# 03_iMX_8X_PMIC.net
KiCad netlist of a schematic drawn in Altium Designer
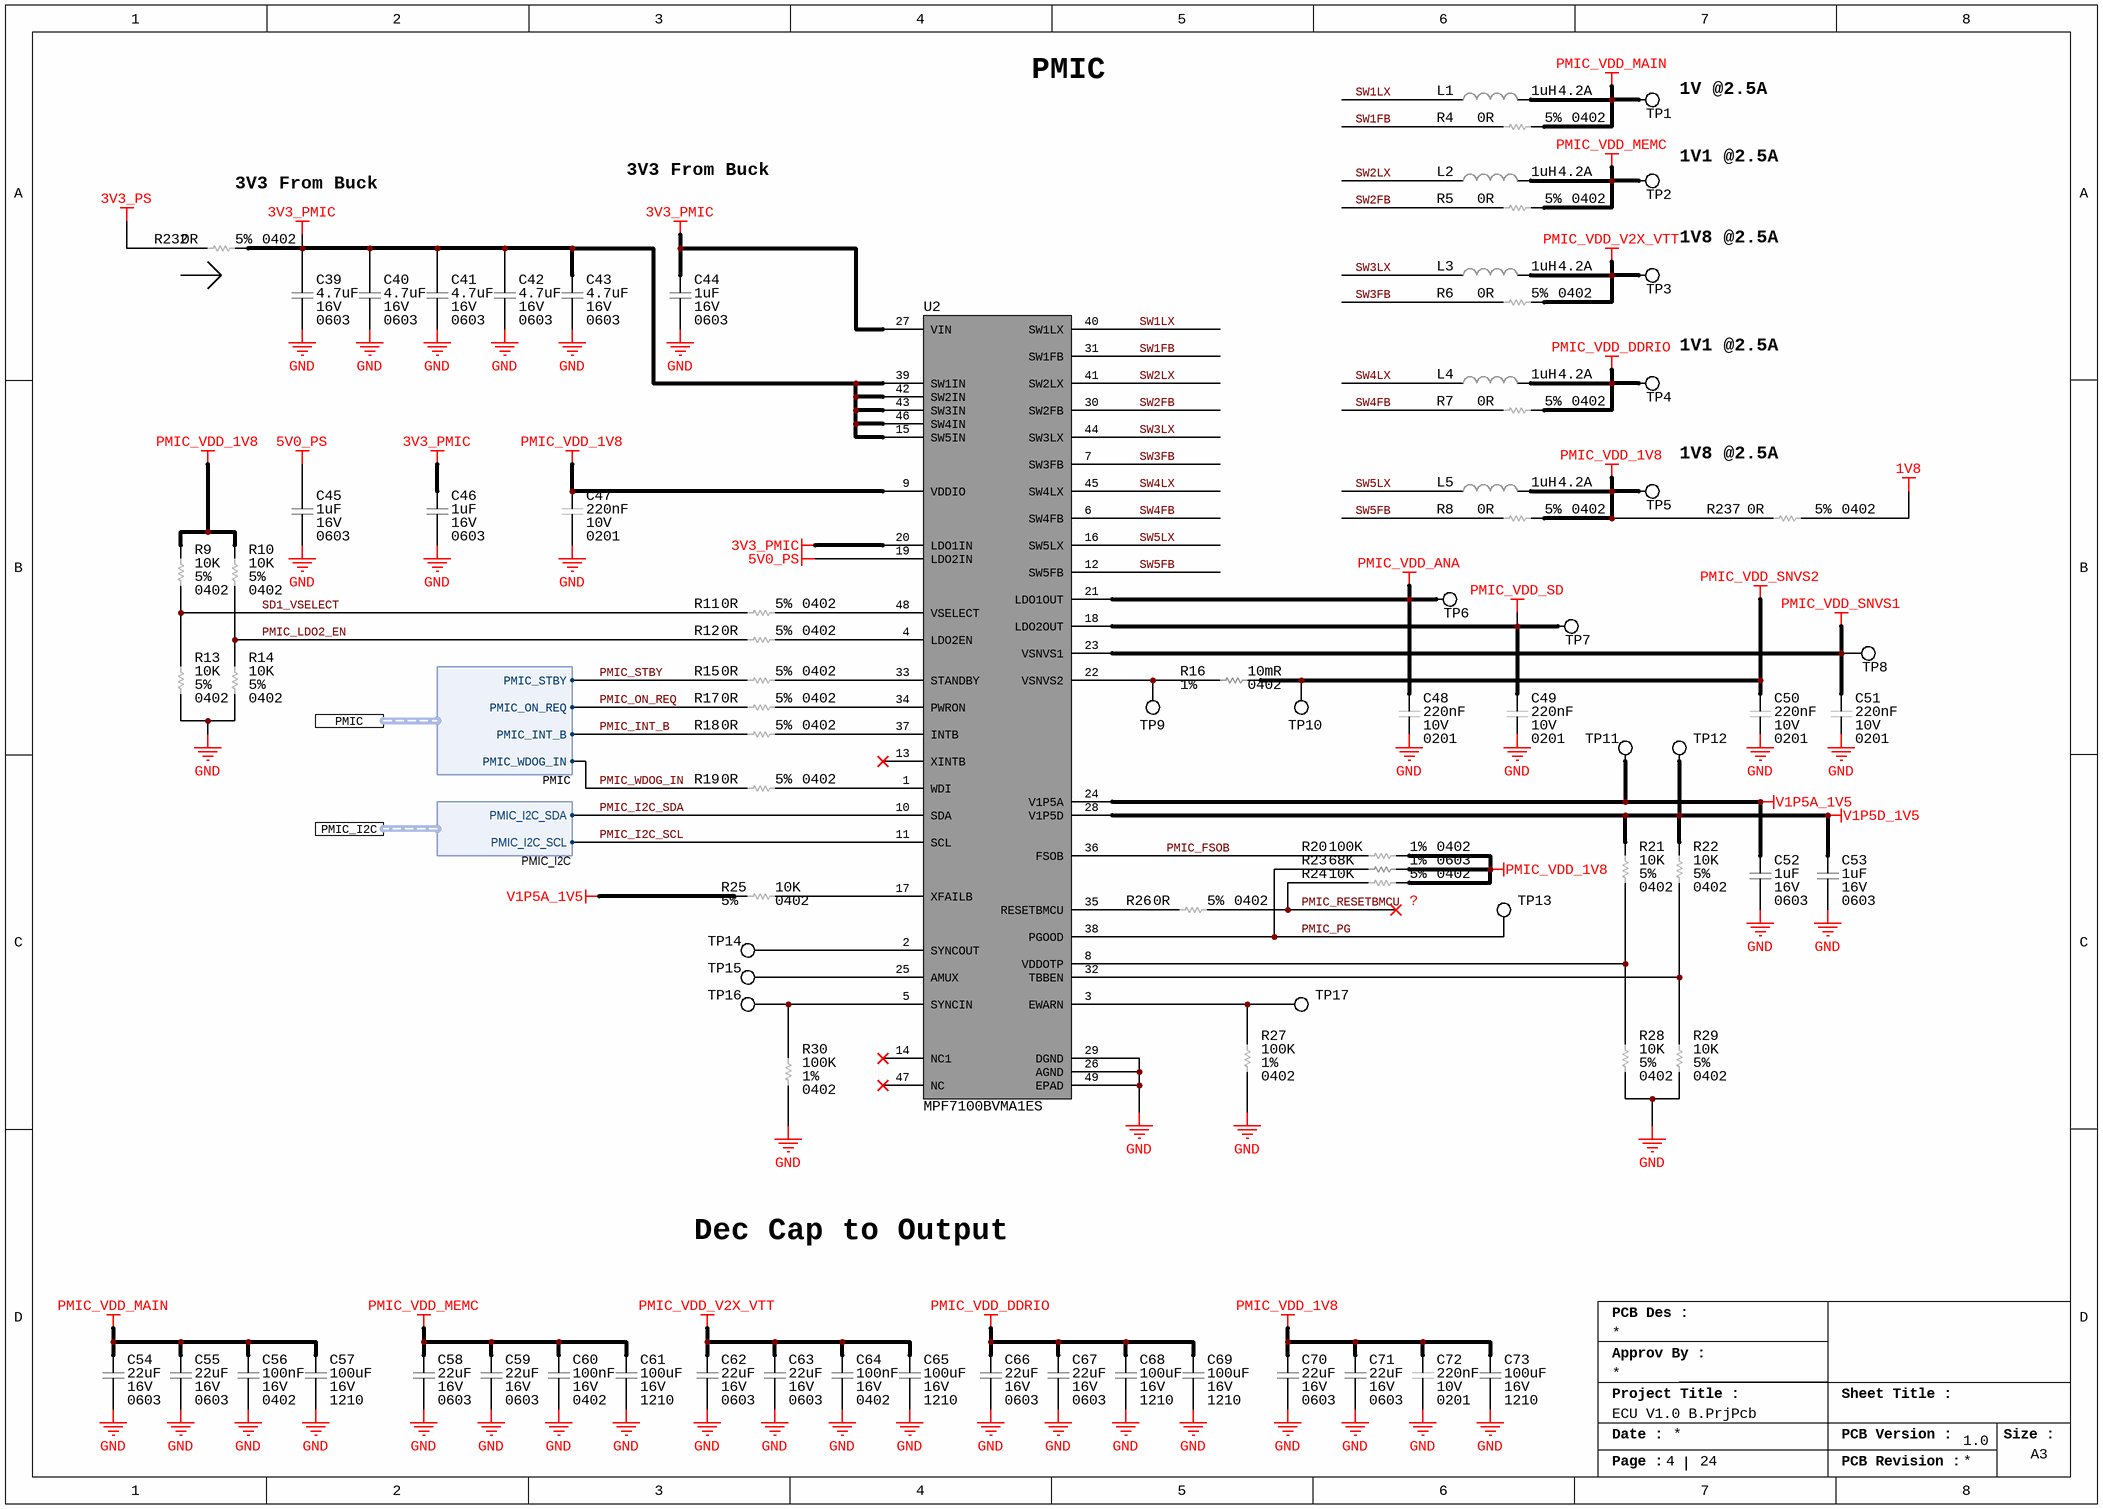
[diagram p0: 03_iMX 8X_PMIC.SchDoc]

(export (version "E")
  (design (tool "Eeschema 10.0.6"))
  (components
    (comp (ref "C39")
      (value "CL10A475KO8NNNC")
      (footprint "CAP_0603_CAPC1608X08N")
      (description "CAP CER 4.7UF 16V X5R 0603")
      (fields
        (field (name "MANUFACTURER") "Samsung")
        (field (name "TOLERANCE") "10%")
        (field (name "VOLTAGE") "16V")
        (field (name "CAPACITANCE") "4.7uF")
        (field (name "CASE/PACKAGE") "0603")
      )
      (libsource (lib "Electronic Devices_LIB") (part "CAP_4.7UF_16V_X5R_0603"))
    )
    (comp (ref "C40")
      (value "CL10A475KO8NNNC")
      (footprint "CAP_0603_CAPC1608X08N")
      (description "CAP CER 4.7UF 16V X5R 0603")
      (fields
        (field (name "MANUFACTURER") "Samsung")
        (field (name "TOLERANCE") "10%")
        (field (name "VOLTAGE") "16V")
        (field (name "CAPACITANCE") "4.7uF")
        (field (name "CASE/PACKAGE") "0603")
      )
      (libsource (lib "Electronic Devices_LIB") (part "CAP_4.7UF_16V_X5R_0603"))
    )
    (comp (ref "C41")
      (value "CL10A475KO8NNNC")
      (footprint "CAP_0603_CAPC1608X08N")
      (description "CAP CER 4.7UF 16V X5R 0603")
      (fields
        (field (name "MANUFACTURER") "Samsung")
        (field (name "TOLERANCE") "10%")
        (field (name "VOLTAGE") "16V")
        (field (name "CAPACITANCE") "4.7uF")
        (field (name "CASE/PACKAGE") "0603")
      )
      (libsource (lib "Electronic Devices_LIB") (part "CAP_4.7UF_16V_X5R_0603"))
    )
    (comp (ref "C42")
      (value "CL10A475KO8NNNC")
      (footprint "CAP_0603_CAPC1608X08N")
      (description "CAP CER 4.7UF 16V X5R 0603")
      (fields
        (field (name "MANUFACTURER") "Samsung")
        (field (name "TOLERANCE") "10%")
        (field (name "VOLTAGE") "16V")
        (field (name "CAPACITANCE") "4.7uF")
        (field (name "CASE/PACKAGE") "0603")
      )
      (libsource (lib "Electronic Devices_LIB") (part "CAP_4.7UF_16V_X5R_0603"))
    )
    (comp (ref "C43")
      (value "CL10A475KO8NNNC")
      (footprint "CAP_0603_CAPC1608X08N")
      (description "CAP CER 4.7UF 16V X5R 0603")
      (fields
        (field (name "MANUFACTURER") "Samsung")
        (field (name "TOLERANCE") "10%")
        (field (name "VOLTAGE") "16V")
        (field (name "CAPACITANCE") "4.7uF")
        (field (name "CASE/PACKAGE") "0603")
      )
      (libsource (lib "Electronic Devices_LIB") (part "CAP_4.7UF_16V_X5R_0603"))
    )
    (comp (ref "C44")
      (value "CL10A105KO8NNNC")
      (footprint "CAP_0603_CAPC1608X08N")
      (description "CAP CER 1UF 16V X5R 0603")
      (fields
        (field (name "MANUFACTURER") "Samsung")
        (field (name "TOLERANCE") "10%")
        (field (name "VOLTAGE RATING") "16V")
        (field (name "CAPACITANCE") "1uF")
        (field (name "CASE/PACKAGE") "0603")
      )
      (libsource (lib "Electronic Devices_LIB") (part "CAP_1UF_16V_X5R_0603"))
    )
    (comp (ref "C45")
      (value "CL10A105KO8NNNC")
      (footprint "CAP_0603_CAPC1608X08N")
      (description "CAP CER 1UF 16V X5R 0603")
      (fields
        (field (name "MANUFACTURER") "Samsung")
        (field (name "TOLERANCE") "10%")
        (field (name "VOLTAGE RATING") "16V")
        (field (name "CAPACITANCE") "1uF")
        (field (name "CASE/PACKAGE") "0603")
      )
      (libsource (lib "Electronic Devices_LIB") (part "CAP_1UF_16V_X5R_0603"))
    )
    (comp (ref "C46")
      (value "CL10A105KO8NNNC")
      (footprint "CAP_0603_CAPC1608X08N")
      (description "CAP CER 1UF 16V X5R 0603")
      (fields
        (field (name "MANUFACTURER") "Samsung")
        (field (name "TOLERANCE") "10%")
        (field (name "VOLTAGE RATING") "16V")
        (field (name "CAPACITANCE") "1uF")
        (field (name "CASE/PACKAGE") "0603")
      )
      (libsource (lib "Electronic Devices_LIB") (part "CAP_1UF_16V_X5R_0603"))
    )
    (comp (ref "C47")
      (value "LMK063BJ224MP-F")
      (footprint "CAP_0201_CAPC0603X03N")
      (description "Multilayer Ceramic Capacitors (High dielectric type), 10V, 0.22 uF, ± 20 %, 0201, X5R, RoHS")
      (fields
        (field (name "MANUFACTURER") "Taiyo Yuden")
        (field (name "TOLERANCE") "20%")
        (field (name "VOLTAGE RATING (DC)") "10V")
        (field (name "CAPACITANCE") "220nF")
        (field (name "CASE/PACKAGE") "0201")
      )
      (libsource (lib "Electronic Devices_LIB") (part "CAP_0.22UF_10V_X5R_0201"))
    )
    (comp (ref "C48")
      (value "LMK063BJ224MP-F")
      (footprint "CAP_0201_CAPC0603X03N")
      (description "Multilayer Ceramic Capacitors (High dielectric type), 10V, 0.22 uF, ± 20 %, 0201, X5R, RoHS")
      (fields
        (field (name "MANUFACTURER") "Taiyo Yuden")
        (field (name "TOLERANCE") "20%")
        (field (name "VOLTAGE RATING (DC)") "10V")
        (field (name "CAPACITANCE") "220nF")
        (field (name "CASE/PACKAGE") "0201")
      )
      (libsource (lib "Electronic Devices_LIB") (part "CAP_0.22UF_10V_X5R_0201"))
    )
    (comp (ref "C49")
      (value "LMK063BJ224MP-F")
      (footprint "CAP_0201_CAPC0603X03N")
      (description "Multilayer Ceramic Capacitors (High dielectric type), 10V, 0.22 uF, ± 20 %, 0201, X5R, RoHS")
      (fields
        (field (name "MANUFACTURER") "Taiyo Yuden")
        (field (name "TOLERANCE") "20%")
        (field (name "VOLTAGE RATING (DC)") "10V")
        (field (name "CAPACITANCE") "220nF")
        (field (name "CASE/PACKAGE") "0201")
      )
      (libsource (lib "Electronic Devices_LIB") (part "CAP_0.22UF_10V_X5R_0201"))
    )
    (comp (ref "C50")
      (value "LMK063BJ224MP-F")
      (footprint "CAP_0201_CAPC0603X03N")
      (description "Multilayer Ceramic Capacitors (High dielectric type), 10V, 0.22 uF, ± 20 %, 0201, X5R, RoHS")
      (fields
        (field (name "MANUFACTURER") "Taiyo Yuden")
        (field (name "TOLERANCE") "20%")
        (field (name "VOLTAGE RATING (DC)") "10V")
        (field (name "CAPACITANCE") "220nF")
        (field (name "CASE/PACKAGE") "0201")
      )
      (libsource (lib "Electronic Devices_LIB") (part "CAP_0.22UF_10V_X5R_0201"))
    )
    (comp (ref "C51")
      (value "LMK063BJ224MP-F")
      (footprint "CAP_0201_CAPC0603X03N")
      (description "Multilayer Ceramic Capacitors (High dielectric type), 10V, 0.22 uF, ± 20 %, 0201, X5R, RoHS")
      (fields
        (field (name "MANUFACTURER") "Taiyo Yuden")
        (field (name "TOLERANCE") "20%")
        (field (name "VOLTAGE RATING (DC)") "10V")
        (field (name "CAPACITANCE") "220nF")
        (field (name "CASE/PACKAGE") "0201")
      )
      (libsource (lib "Electronic Devices_LIB") (part "CAP_0.22UF_10V_X5R_0201"))
    )
    (comp (ref "C52")
      (value "CL10A105KO8NNNC")
      (footprint "CAP_0603_CAPC1608X08N")
      (description "CAP CER 1UF 16V X5R 0603")
      (fields
        (field (name "MANUFACTURER") "Samsung")
        (field (name "TOLERANCE") "10%")
        (field (name "VOLTAGE RATING") "16V")
        (field (name "CAPACITANCE") "1uF")
        (field (name "CASE/PACKAGE") "0603")
      )
      (libsource (lib "Electronic Devices_LIB") (part "CAP_1UF_16V_X5R_0603"))
    )
    (comp (ref "C53")
      (value "CL10A105KO8NNNC")
      (footprint "CAP_0603_CAPC1608X08N")
      (description "CAP CER 1UF 16V X5R 0603")
      (fields
        (field (name "MANUFACTURER") "Samsung")
        (field (name "TOLERANCE") "10%")
        (field (name "VOLTAGE RATING") "16V")
        (field (name "CAPACITANCE") "1uF")
        (field (name "CASE/PACKAGE") "0603")
      )
      (libsource (lib "Electronic Devices_LIB") (part "CAP_1UF_16V_X5R_0603"))
    )
    (comp (ref "C54")
      (value "CL10A226MO7JZNC")
      (footprint "CAP_0603_CAPC1608X08N")
      (description "Cap Ceramic 22uF 16V X5R 20% Pad SMD 0603 85C T/R")
      (fields
        (field (name "MANUFACTURER") "Samsung")
        (field (name "TOLERANCE") "20%")
        (field (name "CAPACITANCE") "22uF")
        (field (name "VOLTAGE RATING") "16V")
        (field (name "CASE/PACKAGE") "0603")
      )
      (libsource (lib "Electronic Devices_LIB") (part "CAP_22UF_16V_X5R_0603"))
    )
    (comp (ref "C55")
      (value "CL10A226MO7JZNC")
      (footprint "CAP_0603_CAPC1608X08N")
      (description "Cap Ceramic 22uF 16V X5R 20% Pad SMD 0603 85C T/R")
      (fields
        (field (name "MANUFACTURER") "Samsung")
        (field (name "TOLERANCE") "20%")
        (field (name "CAPACITANCE") "22uF")
        (field (name "VOLTAGE RATING") "16V")
        (field (name "CASE/PACKAGE") "0603")
      )
      (libsource (lib "Electronic Devices_LIB") (part "CAP_22UF_16V_X5R_0603"))
    )
    (comp (ref "C56")
      (value "CL05B104KO5NNNC")
      (footprint "CAP_0402_CAPC1005X05N")
      (description "Multilayer Ceramic Capacitor, 0.1 uF, 16 V, ± 10%, X7R, 0402 [1005 Metric]")
      (fields
        (field (name "MANUFACTURER") "Samsung")
        (field (name "TOLERANCE") "10%")
        (field (name "VOLTAGE RATING") "16V")
        (field (name "CAPACITANCE") "100nF")
        (field (name "CASE/PACKAGE") "0402")
      )
      (libsource (lib "Electronic Devices_LIB") (part "CAP_100NF_16V_X7R_0402"))
    )
    (comp (ref "C57")
      (value "EMK325ABJ107MM-T")
      (footprint "CAP_1210_CAPC3225X270N")
      (description "Multilayer Ceramic Capacitor, 100 uF, 16 V, ± 20%, X5R, 1210 [3225 Metric]")
      (fields
        (field (name "MANUFACTURER") "Taiyo Yuden")
        (field (name "TOLERANCE") "20%")
        (field (name "VOLTAGE RATING") "16V")
        (field (name "CAPACITANCE") "100uF")
        (field (name "CASE/PACKAGE") "1210")
      )
      (libsource (lib "Electronic Devices_LIB") (part "CAP_100UF_16V_X5R_1210"))
    )
    (comp (ref "C58")
      (value "CL10A226MO7JZNC")
      (footprint "CAP_0603_CAPC1608X08N")
      (description "Cap Ceramic 22uF 16V X5R 20% Pad SMD 0603 85C T/R")
      (fields
        (field (name "MANUFACTURER") "Samsung")
        (field (name "TOLERANCE") "20%")
        (field (name "CAPACITANCE") "22uF")
        (field (name "VOLTAGE RATING") "16V")
        (field (name "CASE/PACKAGE") "0603")
      )
      (libsource (lib "Electronic Devices_LIB") (part "CAP_22UF_16V_X5R_0603"))
    )
    (comp (ref "C59")
      (value "CL10A226MO7JZNC")
      (footprint "CAP_0603_CAPC1608X08N")
      (description "Cap Ceramic 22uF 16V X5R 20% Pad SMD 0603 85C T/R")
      (fields
        (field (name "MANUFACTURER") "Samsung")
        (field (name "TOLERANCE") "20%")
        (field (name "CAPACITANCE") "22uF")
        (field (name "VOLTAGE RATING") "16V")
        (field (name "CASE/PACKAGE") "0603")
      )
      (libsource (lib "Electronic Devices_LIB") (part "CAP_22UF_16V_X5R_0603"))
    )
    (comp (ref "C60")
      (value "CL05B104KO5NNNC")
      (footprint "CAP_0402_CAPC1005X05N")
      (description "Multilayer Ceramic Capacitor, 0.1 uF, 16 V, ± 10%, X7R, 0402 [1005 Metric]")
      (fields
        (field (name "MANUFACTURER") "Samsung")
        (field (name "TOLERANCE") "10%")
        (field (name "VOLTAGE RATING") "16V")
        (field (name "CAPACITANCE") "100nF")
        (field (name "CASE/PACKAGE") "0402")
      )
      (libsource (lib "Electronic Devices_LIB") (part "CAP_100NF_16V_X7R_0402"))
    )
    (comp (ref "C61")
      (value "EMK325ABJ107MM-T")
      (footprint "CAP_1210_CAPC3225X270N")
      (description "Multilayer Ceramic Capacitor, 100 uF, 16 V, ± 20%, X5R, 1210 [3225 Metric]")
      (fields
        (field (name "MANUFACTURER") "Taiyo Yuden")
        (field (name "TOLERANCE") "20%")
        (field (name "VOLTAGE RATING") "16V")
        (field (name "CAPACITANCE") "100uF")
        (field (name "CASE/PACKAGE") "1210")
      )
      (libsource (lib "Electronic Devices_LIB") (part "CAP_100UF_16V_X5R_1210"))
    )
    (comp (ref "C62")
      (value "CL10A226MO7JZNC")
      (footprint "CAP_0603_CAPC1608X08N")
      (description "Cap Ceramic 22uF 16V X5R 20% Pad SMD 0603 85C T/R")
      (fields
        (field (name "MANUFACTURER") "Samsung")
        (field (name "TOLERANCE") "20%")
        (field (name "CAPACITANCE") "22uF")
        (field (name "VOLTAGE RATING") "16V")
        (field (name "CASE/PACKAGE") "0603")
      )
      (libsource (lib "Electronic Devices_LIB") (part "CAP_22UF_16V_X5R_0603"))
    )
    (comp (ref "C63")
      (value "CL10A226MO7JZNC")
      (footprint "CAP_0603_CAPC1608X08N")
      (description "Cap Ceramic 22uF 16V X5R 20% Pad SMD 0603 85C T/R")
      (fields
        (field (name "MANUFACTURER") "Samsung")
        (field (name "TOLERANCE") "20%")
        (field (name "CAPACITANCE") "22uF")
        (field (name "VOLTAGE RATING") "16V")
        (field (name "CASE/PACKAGE") "0603")
      )
      (libsource (lib "Electronic Devices_LIB") (part "CAP_22UF_16V_X5R_0603"))
    )
    (comp (ref "C64")
      (value "CL05B104KO5NNNC")
      (footprint "CAP_0402_CAPC1005X05N")
      (description "Multilayer Ceramic Capacitor, 0.1 uF, 16 V, ± 10%, X7R, 0402 [1005 Metric]")
      (fields
        (field (name "MANUFACTURER") "Samsung")
        (field (name "TOLERANCE") "10%")
        (field (name "VOLTAGE RATING") "16V")
        (field (name "CAPACITANCE") "100nF")
        (field (name "CASE/PACKAGE") "0402")
      )
      (libsource (lib "Electronic Devices_LIB") (part "CAP_100NF_16V_X7R_0402"))
    )
    (comp (ref "C65")
      (value "EMK325ABJ107MM-T")
      (footprint "CAP_1210_CAPC3225X270N")
      (description "Multilayer Ceramic Capacitor, 100 uF, 16 V, ± 20%, X5R, 1210 [3225 Metric]")
      (fields
        (field (name "MANUFACTURER") "Taiyo Yuden")
        (field (name "TOLERANCE") "20%")
        (field (name "VOLTAGE RATING") "16V")
        (field (name "CAPACITANCE") "100uF")
        (field (name "CASE/PACKAGE") "1210")
      )
      (libsource (lib "Electronic Devices_LIB") (part "CAP_100UF_16V_X5R_1210"))
    )
    (comp (ref "C66")
      (value "CL10A226MO7JZNC")
      (footprint "CAP_0603_CAPC1608X08N")
      (description "Cap Ceramic 22uF 16V X5R 20% Pad SMD 0603 85C T/R")
      (fields
        (field (name "MANUFACTURER") "Samsung")
        (field (name "TOLERANCE") "20%")
        (field (name "CAPACITANCE") "22uF")
        (field (name "VOLTAGE RATING") "16V")
        (field (name "CASE/PACKAGE") "0603")
      )
      (libsource (lib "Electronic Devices_LIB") (part "CAP_22UF_16V_X5R_0603"))
    )
    (comp (ref "C67")
      (value "CL10A226MO7JZNC")
      (footprint "CAP_0603_CAPC1608X08N")
      (description "Cap Ceramic 22uF 16V X5R 20% Pad SMD 0603 85C T/R")
      (fields
        (field (name "MANUFACTURER") "Samsung")
        (field (name "TOLERANCE") "20%")
        (field (name "CAPACITANCE") "22uF")
        (field (name "VOLTAGE RATING") "16V")
        (field (name "CASE/PACKAGE") "0603")
      )
      (libsource (lib "Electronic Devices_LIB") (part "CAP_22UF_16V_X5R_0603"))
    )
    (comp (ref "C68")
      (value "EMK325ABJ107MM-T")
      (footprint "CAP_1210_CAPC3225X270N")
      (description "Multilayer Ceramic Capacitor, 100 uF, 16 V, ± 20%, X5R, 1210 [3225 Metric]")
      (fields
        (field (name "MANUFACTURER") "Taiyo Yuden")
        (field (name "TOLERANCE") "20%")
        (field (name "VOLTAGE RATING") "16V")
        (field (name "CAPACITANCE") "100uF")
        (field (name "CASE/PACKAGE") "1210")
      )
      (libsource (lib "Electronic Devices_LIB") (part "CAP_100UF_16V_X5R_1210"))
    )
    (comp (ref "C69")
      (value "EMK325ABJ107MM-T")
      (footprint "CAP_1210_CAPC3225X270N")
      (description "Multilayer Ceramic Capacitor, 100 uF, 16 V, ± 20%, X5R, 1210 [3225 Metric]")
      (fields
        (field (name "MANUFACTURER") "Taiyo Yuden")
        (field (name "TOLERANCE") "20%")
        (field (name "VOLTAGE RATING") "16V")
        (field (name "CAPACITANCE") "100uF")
        (field (name "CASE/PACKAGE") "1210")
      )
      (libsource (lib "Electronic Devices_LIB") (part "CAP_100UF_16V_X5R_1210"))
    )
    (comp (ref "C70")
      (value "CL10A226MO7JZNC")
      (footprint "CAP_0603_CAPC1608X08N")
      (description "Cap Ceramic 22uF 16V X5R 20% Pad SMD 0603 85C T/R")
      (fields
        (field (name "MANUFACTURER") "Samsung")
        (field (name "TOLERANCE") "20%")
        (field (name "CAPACITANCE") "22uF")
        (field (name "VOLTAGE RATING") "16V")
        (field (name "CASE/PACKAGE") "0603")
      )
      (libsource (lib "Electronic Devices_LIB") (part "CAP_22UF_16V_X5R_0603"))
    )
    (comp (ref "C71")
      (value "CL10A226MO7JZNC")
      (footprint "CAP_0603_CAPC1608X08N")
      (description "Cap Ceramic 22uF 16V X5R 20% Pad SMD 0603 85C T/R")
      (fields
        (field (name "MANUFACTURER") "Samsung")
        (field (name "TOLERANCE") "20%")
        (field (name "CAPACITANCE") "22uF")
        (field (name "VOLTAGE RATING") "16V")
        (field (name "CASE/PACKAGE") "0603")
      )
      (libsource (lib "Electronic Devices_LIB") (part "CAP_22UF_16V_X5R_0603"))
    )
    (comp (ref "C72")
      (value "LMK063BJ224MP-F")
      (footprint "CAP_0201_CAPC0603X03N")
      (description "Multilayer Ceramic Capacitors (High dielectric type), 10V, 0.22 uF, ± 20 %, 0201, X5R, RoHS")
      (fields
        (field (name "MANUFACTURER") "Taiyo Yuden")
        (field (name "TOLERANCE") "20%")
        (field (name "VOLTAGE RATING (DC)") "10V")
        (field (name "CAPACITANCE") "220nF")
        (field (name "CASE/PACKAGE") "0201")
      )
      (libsource (lib "Electronic Devices_LIB") (part "CAP_0.22UF_10V_X5R_0201"))
    )
    (comp (ref "C73")
      (value "EMK325ABJ107MM-T")
      (footprint "CAP_1210_CAPC3225X270N")
      (description "Multilayer Ceramic Capacitor, 100 uF, 16 V, ± 20%, X5R, 1210 [3225 Metric]")
      (fields
        (field (name "MANUFACTURER") "Taiyo Yuden")
        (field (name "TOLERANCE") "20%")
        (field (name "VOLTAGE RATING") "16V")
        (field (name "CAPACITANCE") "100uF")
        (field (name "CASE/PACKAGE") "1210")
      )
      (libsource (lib "Electronic Devices_LIB") (part "CAP_100UF_16V_X5R_1210"))
    )
    (comp (ref "L1")
      (value "TFM252012ALMA1R0MTAA")
      (footprint "INDC2520X120N")
      (description "Inductor Power Shielded Thin Film 1uH 20% 1MHz Metal 3.7A 0.042Ohm DCR 1008 Automotive T/R")
      (fields
        (field (name "MANUFACTURER") "TDK")
        (field (name "TOLERANCE") "20%")
        (field (name "SATURATION CURRENT") "4.2A")
        (field (name "INDUCTANCE") "1uH")
      )
      (libsource (lib "Electronic Devices_LIB") (part "IND_1uH_3.7A_TFM252012ALMA1R0MTAA"))
    )
    (comp (ref "L2")
      (value "TFM252012ALMA1R0MTAA")
      (footprint "INDC2520X120N")
      (description "Inductor Power Shielded Thin Film 1uH 20% 1MHz Metal 3.7A 0.042Ohm DCR 1008 Automotive T/R")
      (fields
        (field (name "MANUFACTURER") "TDK")
        (field (name "TOLERANCE") "20%")
        (field (name "SATURATION CURRENT") "4.2A")
        (field (name "INDUCTANCE") "1uH")
      )
      (libsource (lib "Electronic Devices_LIB") (part "IND_1uH_3.7A_TFM252012ALMA1R0MTAA"))
    )
    (comp (ref "L3")
      (value "TFM252012ALMA1R0MTAA")
      (footprint "INDC2520X120N")
      (description "Inductor Power Shielded Thin Film 1uH 20% 1MHz Metal 3.7A 0.042Ohm DCR 1008 Automotive T/R")
      (fields
        (field (name "MANUFACTURER") "TDK")
        (field (name "TOLERANCE") "20%")
        (field (name "SATURATION CURRENT") "4.2A")
        (field (name "INDUCTANCE") "1uH")
      )
      (libsource (lib "Electronic Devices_LIB") (part "IND_1uH_3.7A_TFM252012ALMA1R0MTAA"))
    )
    (comp (ref "L4")
      (value "TFM252012ALMA1R0MTAA")
      (footprint "INDC2520X120N")
      (description "Inductor Power Shielded Thin Film 1uH 20% 1MHz Metal 3.7A 0.042Ohm DCR 1008 Automotive T/R")
      (fields
        (field (name "MANUFACTURER") "TDK")
        (field (name "TOLERANCE") "20%")
        (field (name "SATURATION CURRENT") "4.2A")
        (field (name "INDUCTANCE") "1uH")
      )
      (libsource (lib "Electronic Devices_LIB") (part "IND_1uH_3.7A_TFM252012ALMA1R0MTAA"))
    )
    (comp (ref "L5")
      (value "TFM252012ALMA1R0MTAA")
      (footprint "INDC2520X120N")
      (description "Inductor Power Shielded Thin Film 1uH 20% 1MHz Metal 3.7A 0.042Ohm DCR 1008 Automotive T/R")
      (fields
        (field (name "MANUFACTURER") "TDK")
        (field (name "TOLERANCE") "20%")
        (field (name "SATURATION CURRENT") "4.2A")
        (field (name "INDUCTANCE") "1uH")
      )
      (libsource (lib "Electronic Devices_LIB") (part "IND_1uH_3.7A_TFM252012ALMA1R0MTAA"))
    )
    (comp (ref "R4")
      (value "ERJ-2GE0R00X")
      (footprint "RES_0402_RESC1005X04N")
      (description "SMD Chip Resistor, Jumper, 0 ohm, 100 mW, 0402 [1005 Metric], Thick Film, General Purpose")
      (fields
        (field (name "MANUFACTURER") "Panasonic")
        (field (name "CASE CODE (IMPERIAL)") "0402")
        (field (name "TOLERANCE") "5%")
        (field (name "RESISTANCE") "0R")
      )
      (libsource (lib "Electronic Devices_LIB") (part "RES_0R_5%_100mW_0402"))
    )
    (comp (ref "R5")
      (value "ERJ-2GE0R00X")
      (footprint "RES_0402_RESC1005X04N")
      (description "SMD Chip Resistor, Jumper, 0 ohm, 100 mW, 0402 [1005 Metric], Thick Film, General Purpose")
      (fields
        (field (name "MANUFACTURER") "Panasonic")
        (field (name "CASE CODE (IMPERIAL)") "0402")
        (field (name "TOLERANCE") "5%")
        (field (name "RESISTANCE") "0R")
      )
      (libsource (lib "Electronic Devices_LIB") (part "RES_0R_5%_100mW_0402"))
    )
    (comp (ref "R6")
      (value "ERJ-2GE0R00X")
      (footprint "RES_0402_RESC1005X04N")
      (description "SMD Chip Resistor, Jumper, 0 ohm, 100 mW, 0402 [1005 Metric], Thick Film, General Purpose")
      (fields
        (field (name "MANUFACTURER") "Panasonic")
        (field (name "CASE CODE (IMPERIAL)") "0402")
        (field (name "TOLERANCE") "5%")
        (field (name "RESISTANCE") "0R")
      )
      (libsource (lib "Electronic Devices_LIB") (part "RES_0R_5%_100mW_0402"))
    )
    (comp (ref "R7")
      (value "ERJ-2GE0R00X")
      (footprint "RES_0402_RESC1005X04N")
      (description "SMD Chip Resistor, Jumper, 0 ohm, 100 mW, 0402 [1005 Metric], Thick Film, General Purpose")
      (fields
        (field (name "MANUFACTURER") "Panasonic")
        (field (name "CASE CODE (IMPERIAL)") "0402")
        (field (name "TOLERANCE") "5%")
        (field (name "RESISTANCE") "0R")
      )
      (libsource (lib "Electronic Devices_LIB") (part "RES_0R_5%_100mW_0402"))
    )
    (comp (ref "R8")
      (value "ERJ-2GE0R00X")
      (footprint "RES_0402_RESC1005X04N")
      (description "SMD Chip Resistor, Jumper, 0 ohm, 100 mW, 0402 [1005 Metric], Thick Film, General Purpose")
      (fields
        (field (name "MANUFACTURER") "Panasonic")
        (field (name "CASE CODE (IMPERIAL)") "0402")
        (field (name "TOLERANCE") "5%")
        (field (name "RESISTANCE") "0R")
      )
      (libsource (lib "Electronic Devices_LIB") (part "RES_0R_5%_100mW_0402"))
    )
    (comp (ref "R9")
      (value "ERJ-2GEJ103X")
      (footprint "RES_0402_RESC1005X04N")
      (description "Res Thick Film 0402 10K Ohm 5% 1/10W ±200ppm/°C Molded SMD Punched Carrier T/R")
      (fields
        (field (name "MANUFACTURER") "Panasonic")
        (field (name "TOLERANCE") "5%")
        (field (name "RESISTANCE") "10K")
        (field (name "CASE/PACKAGE") "0402")
      )
      (libsource (lib "Electronic Devices_LIB") (part "RES_10K_5%_100mW_0402"))
    )
    (comp (ref "R10")
      (value "ERJ-2GEJ103X")
      (footprint "RES_0402_RESC1005X04N")
      (description "Res Thick Film 0402 10K Ohm 5% 1/10W ±200ppm/°C Molded SMD Punched Carrier T/R")
      (fields
        (field (name "MANUFACTURER") "Panasonic")
        (field (name "TOLERANCE") "5%")
        (field (name "RESISTANCE") "10K")
        (field (name "CASE/PACKAGE") "0402")
      )
      (libsource (lib "Electronic Devices_LIB") (part "RES_10K_5%_100mW_0402"))
    )
    (comp (ref "R11")
      (value "ERJ-2GE0R00X")
      (footprint "RES_0402_RESC1005X04N")
      (description "SMD Chip Resistor, Jumper, 0 ohm, 100 mW, 0402 [1005 Metric], Thick Film, General Purpose")
      (fields
        (field (name "MANUFACTURER") "Panasonic")
        (field (name "CASE CODE (IMPERIAL)") "0402")
        (field (name "TOLERANCE") "5%")
        (field (name "RESISTANCE") "0R")
      )
      (libsource (lib "Electronic Devices_LIB") (part "RES_0R_5%_100mW_0402"))
    )
    (comp (ref "R12")
      (value "ERJ-2GE0R00X")
      (footprint "RES_0402_RESC1005X04N")
      (description "SMD Chip Resistor, Jumper, 0 ohm, 100 mW, 0402 [1005 Metric], Thick Film, General Purpose")
      (fields
        (field (name "MANUFACTURER") "Panasonic")
        (field (name "CASE CODE (IMPERIAL)") "0402")
        (field (name "TOLERANCE") "5%")
        (field (name "RESISTANCE") "0R")
      )
      (libsource (lib "Electronic Devices_LIB") (part "RES_0R_5%_100mW_0402"))
    )
    (comp (ref "R13")
      (value "ERJ-2GEJ103X")
      (footprint "RES_0402_RESC1005X04N")
      (description "Res Thick Film 0402 10K Ohm 5% 1/10W ±200ppm/°C Molded SMD Punched Carrier T/R")
      (fields
        (field (name "MANUFACTURER") "Panasonic")
        (field (name "TOLERANCE") "5%")
        (field (name "RESISTANCE") "10K")
        (field (name "CASE/PACKAGE") "0402")
      )
      (libsource (lib "Electronic Devices_LIB") (part "RES_10K_5%_100mW_0402"))
    )
    (comp (ref "R14")
      (value "ERJ-2GEJ103X")
      (footprint "RES_0402_RESC1005X04N")
      (description "Res Thick Film 0402 10K Ohm 5% 1/10W ±200ppm/°C Molded SMD Punched Carrier T/R")
      (fields
        (field (name "MANUFACTURER") "Panasonic")
        (field (name "TOLERANCE") "5%")
        (field (name "RESISTANCE") "10K")
        (field (name "CASE/PACKAGE") "0402")
      )
      (libsource (lib "Electronic Devices_LIB") (part "RES_10K_5%_100mW_0402"))
    )
    (comp (ref "R15")
      (value "ERJ-2GE0R00X")
      (footprint "RES_0402_RESC1005X04N")
      (description "SMD Chip Resistor, Jumper, 0 ohm, 100 mW, 0402 [1005 Metric], Thick Film, General Purpose")
      (fields
        (field (name "MANUFACTURER") "Panasonic")
        (field (name "CASE CODE (IMPERIAL)") "0402")
        (field (name "TOLERANCE") "5%")
        (field (name "RESISTANCE") "0R")
      )
      (libsource (lib "Electronic Devices_LIB") (part "RES_0R_5%_100mW_0402"))
    )
    (comp (ref "R16")
      (value "ERJ-2LWFR010X")
      (footprint "RES_0603_RESC1608X04N")
      (description "Res Current Sense Thick Film 0402 0.01 Ohm 1% 1/5W 0ppm/°C to 500ppm/°C Molded T/R")
      (fields
        (field (name "MANUFACTURER") "Panasonic")
        (field (name "TOLERANCE") "1%")
        (field (name "RESISTANCE") "10mR")
        (field (name "CASE/PACKAGE") "0402")
      )
      (libsource (lib "Electronic Devices_LIB") (part "RES_10mR_1%_0.05W_0402"))
    )
    (comp (ref "R17")
      (value "ERJ-2GE0R00X")
      (footprint "RES_0402_RESC1005X04N")
      (description "SMD Chip Resistor, Jumper, 0 ohm, 100 mW, 0402 [1005 Metric], Thick Film, General Purpose")
      (fields
        (field (name "MANUFACTURER") "Panasonic")
        (field (name "CASE CODE (IMPERIAL)") "0402")
        (field (name "TOLERANCE") "5%")
        (field (name "RESISTANCE") "0R")
      )
      (libsource (lib "Electronic Devices_LIB") (part "RES_0R_5%_100mW_0402"))
    )
    (comp (ref "R18")
      (value "ERJ-2GE0R00X")
      (footprint "RES_0402_RESC1005X04N")
      (description "SMD Chip Resistor, Jumper, 0 ohm, 100 mW, 0402 [1005 Metric], Thick Film, General Purpose")
      (fields
        (field (name "MANUFACTURER") "Panasonic")
        (field (name "CASE CODE (IMPERIAL)") "0402")
        (field (name "TOLERANCE") "5%")
        (field (name "RESISTANCE") "0R")
      )
      (libsource (lib "Electronic Devices_LIB") (part "RES_0R_5%_100mW_0402"))
    )
    (comp (ref "R19")
      (value "ERJ-2GE0R00X")
      (footprint "RES_0402_RESC1005X04N")
      (description "SMD Chip Resistor, Jumper, 0 ohm, 100 mW, 0402 [1005 Metric], Thick Film, General Purpose")
      (fields
        (field (name "MANUFACTURER") "Panasonic")
        (field (name "CASE CODE (IMPERIAL)") "0402")
        (field (name "TOLERANCE") "5%")
        (field (name "RESISTANCE") "0R")
      )
      (libsource (lib "Electronic Devices_LIB") (part "RES_0R_5%_100mW_0402"))
    )
    (comp (ref "R20")
      (value "RC0402FR-07100KL")
      (footprint "RES_0402_RESC1005X04N")
      (description "SMD Chip Resistor, 100 kOhm, ± 1%, 63 mW, 0402 [1005 Metric], Thick Film, General Purpose")
      (fields
        (field (name "MANUFACTURER") "Yageo")
        (field (name "RESISTANCE") "100K")
        (field (name "TOLERANCE") "1%")
        (field (name "CASE/PACKAGE") "0402")
      )
      (libsource (lib "Electronic Devices_LIB") (part "RES_100K_1%_100mW_0402"))
    )
    (comp (ref "R21")
      (value "ERJ-2GEJ103X")
      (footprint "RES_0402_RESC1005X04N")
      (description "Res Thick Film 0402 10K Ohm 5% 1/10W ±200ppm/°C Molded SMD Punched Carrier T/R")
      (fields
        (field (name "MANUFACTURER") "Panasonic")
        (field (name "TOLERANCE") "5%")
        (field (name "RESISTANCE") "10K")
        (field (name "CASE/PACKAGE") "0402")
      )
      (libsource (lib "Electronic Devices_LIB") (part "RES_10K_5%_100mW_0402"))
    )
    (comp (ref "R22")
      (value "ERJ-2GEJ103X")
      (footprint "RES_0402_RESC1005X04N")
      (description "Res Thick Film 0402 10K Ohm 5% 1/10W ±200ppm/°C Molded SMD Punched Carrier T/R")
      (fields
        (field (name "MANUFACTURER") "Panasonic")
        (field (name "TOLERANCE") "5%")
        (field (name "RESISTANCE") "10K")
        (field (name "CASE/PACKAGE") "0402")
      )
      (libsource (lib "Electronic Devices_LIB") (part "RES_10K_5%_100mW_0402"))
    )
    (comp (ref "R23")
      (value "RC0603FR-0768KL")
      (footprint "RES_0603_RESC1608X04N")
      (description "SMD Chip Resistor, 68 kOhm, ± 1%, 100 mW, 0603 [1608 Metric], Thick Film, General Purpose")
      (fields
        (field (name "MANUFACTURER") "Yageo")
        (field (name "TOLERANCE") "1%")
        (field (name "RESISTANCE") "68K")
        (field (name "CASE/PACKAGE") "0603")
      )
      (libsource (lib "Electronic Devices_LIB") (part "RES_68K_1%_100mW_0603"))
    )
    (comp (ref "R24")
      (value "ERJ-2GEJ103X")
      (footprint "RES_0402_RESC1005X04N")
      (description "Res Thick Film 0402 10K Ohm 5% 1/10W ±200ppm/°C Molded SMD Punched Carrier T/R")
      (fields
        (field (name "MANUFACTURER") "Panasonic")
        (field (name "TOLERANCE") "5%")
        (field (name "RESISTANCE") "10K")
        (field (name "CASE/PACKAGE") "0402")
      )
      (libsource (lib "Electronic Devices_LIB") (part "RES_10K_5%_100mW_0402"))
    )
    (comp (ref "R25")
      (value "ERJ-2GEJ103X")
      (footprint "RES_0402_RESC1005X04N")
      (description "Res Thick Film 0402 10K Ohm 5% 1/10W ±200ppm/°C Molded SMD Punched Carrier T/R")
      (fields
        (field (name "MANUFACTURER") "Panasonic")
        (field (name "TOLERANCE") "5%")
        (field (name "RESISTANCE") "10K")
        (field (name "CASE/PACKAGE") "0402")
      )
      (libsource (lib "Electronic Devices_LIB") (part "RES_10K_5%_100mW_0402"))
    )
    (comp (ref "R26")
      (value "ERJ-2GE0R00X")
      (footprint "RES_0402_RESC1005X04N")
      (description "SMD Chip Resistor, Jumper, 0 ohm, 100 mW, 0402 [1005 Metric], Thick Film, General Purpose")
      (fields
        (field (name "MANUFACTURER") "Panasonic")
        (field (name "CASE CODE (IMPERIAL)") "0402")
        (field (name "TOLERANCE") "5%")
        (field (name "RESISTANCE") "0R")
      )
      (libsource (lib "Electronic Devices_LIB") (part "RES_0R_5%_100mW_0402"))
    )
    (comp (ref "R27")
      (value "RC0402FR-07100KL")
      (footprint "RES_0402_RESC1005X04N")
      (description "SMD Chip Resistor, 100 kOhm, ± 1%, 63 mW, 0402 [1005 Metric], Thick Film, General Purpose")
      (fields
        (field (name "MANUFACTURER") "Yageo")
        (field (name "RESISTANCE") "100K")
        (field (name "TOLERANCE") "1%")
        (field (name "CASE/PACKAGE") "0402")
      )
      (libsource (lib "Electronic Devices_LIB") (part "RES_100K_1%_100mW_0402"))
    )
    (comp (ref "R28")
      (value "ERJ-2GEJ103X")
      (footprint "RES_0402_RESC1005X04N")
      (description "Res Thick Film 0402 10K Ohm 5% 1/10W ±200ppm/°C Molded SMD Punched Carrier T/R")
      (fields
        (field (name "MANUFACTURER") "Panasonic")
        (field (name "TOLERANCE") "5%")
        (field (name "RESISTANCE") "10K")
        (field (name "CASE/PACKAGE") "0402")
      )
      (libsource (lib "Electronic Devices_LIB") (part "RES_10K_5%_100mW_0402"))
    )
    (comp (ref "R29")
      (value "ERJ-2GEJ103X")
      (footprint "RES_0402_RESC1005X04N")
      (description "Res Thick Film 0402 10K Ohm 5% 1/10W ±200ppm/°C Molded SMD Punched Carrier T/R")
      (fields
        (field (name "MANUFACTURER") "Panasonic")
        (field (name "TOLERANCE") "5%")
        (field (name "RESISTANCE") "10K")
        (field (name "CASE/PACKAGE") "0402")
      )
      (libsource (lib "Electronic Devices_LIB") (part "RES_10K_5%_100mW_0402"))
    )
    (comp (ref "R30")
      (value "RC0402FR-07100KL")
      (footprint "RES_0402_RESC1005X04N")
      (description "SMD Chip Resistor, 100 kOhm, ± 1%, 63 mW, 0402 [1005 Metric], Thick Film, General Purpose")
      (fields
        (field (name "MANUFACTURER") "Yageo")
        (field (name "RESISTANCE") "100K")
        (field (name "TOLERANCE") "1%")
        (field (name "CASE/PACKAGE") "0402")
      )
      (libsource (lib "Electronic Devices_LIB") (part "RES_100K_1%_100mW_0402"))
    )
    (comp (ref "R232")
      (value "ERJ-2GE0R00X")
      (footprint "RES_0402_RESC1005X04N")
      (description "SMD Chip Resistor, Jumper, 0 ohm, 100 mW, 0402 [1005 Metric], Thick Film, General Purpose")
      (fields
        (field (name "MANUFACTURER") "Panasonic")
        (field (name "CASE CODE (IMPERIAL)") "0402")
        (field (name "TOLERANCE") "5%")
        (field (name "RESISTANCE") "0R")
      )
      (libsource (lib "Electronic Devices_LIB") (part "RES_0R_5%_100mW_0402"))
    )
    (comp (ref "R237")
      (value "ERJ-2GE0R00X")
      (footprint "RES_0402_RESC1005X04N")
      (description "SMD Chip Resistor, Jumper, 0 ohm, 100 mW, 0402 [1005 Metric], Thick Film, General Purpose")
      (fields
        (field (name "MANUFACTURER") "Panasonic")
        (field (name "CASE CODE (IMPERIAL)") "0402")
        (field (name "TOLERANCE") "5%")
        (field (name "RESISTANCE") "0R")
      )
      (libsource (lib "Electronic Devices_LIB") (part "RES_0R_5%_100mW_0402"))
    )
    (comp (ref "TP1")
      (value "NO COMPONENT")
      (footprint "TP_PAD_0.5MM_SMD_ROUND")
      (description "Test Point, SMD pad, round, 1.5mm, 1.6mm, 3mm diameter")
      (libsource (lib "Electronic Devices_LIB") (part "TP_PAD_SMD_SMALL"))
    )
    (comp (ref "TP2")
      (value "NO COMPONENT")
      (footprint "TP_PAD_0.5MM_SMD_ROUND")
      (description "Test Point, SMD pad, round, 1.5mm, 1.6mm, 3mm diameter")
      (libsource (lib "Electronic Devices_LIB") (part "TP_PAD_SMD_SMALL"))
    )
    (comp (ref "TP3")
      (value "NO COMPONENT")
      (footprint "TP_PAD_0.5MM_SMD_ROUND")
      (description "Test Point, SMD pad, round, 1.5mm, 1.6mm, 3mm diameter")
      (libsource (lib "Electronic Devices_LIB") (part "TP_PAD_SMD_SMALL"))
    )
    (comp (ref "TP4")
      (value "NO COMPONENT")
      (footprint "TP_PAD_0.5MM_SMD_ROUND")
      (description "Test Point, SMD pad, round, 1.5mm, 1.6mm, 3mm diameter")
      (libsource (lib "Electronic Devices_LIB") (part "TP_PAD_SMD_SMALL"))
    )
    (comp (ref "TP5")
      (value "NO COMPONENT")
      (footprint "TP_PAD_0.5MM_SMD_ROUND")
      (description "Test Point, SMD pad, round, 1.5mm, 1.6mm, 3mm diameter")
      (libsource (lib "Electronic Devices_LIB") (part "TP_PAD_SMD_SMALL"))
    )
    (comp (ref "TP6")
      (value "NO COMPONENT")
      (footprint "TP_PAD_0.5MM_SMD_ROUND")
      (description "Test Point, SMD pad, round, 1.5mm, 1.6mm, 3mm diameter")
      (libsource (lib "Electronic Devices_LIB") (part "TP_PAD_SMD_SMALL"))
    )
    (comp (ref "TP7")
      (value "NO COMPONENT")
      (footprint "TP_PAD_0.5MM_SMD_ROUND")
      (description "Test Point, SMD pad, round, 1.5mm, 1.6mm, 3mm diameter")
      (libsource (lib "Electronic Devices_LIB") (part "TP_PAD_SMD_SMALL"))
    )
    (comp (ref "TP8")
      (value "NO COMPONENT")
      (footprint "TP_PAD_0.5MM_SMD_ROUND")
      (description "Test Point, SMD pad, round, 1.5mm, 1.6mm, 3mm diameter")
      (libsource (lib "Electronic Devices_LIB") (part "TP_PAD_SMD_SMALL"))
    )
    (comp (ref "TP9")
      (value "NO COMPONENT")
      (footprint "TP_PAD_0.5MM_SMD_ROUND")
      (description "Test Point, SMD pad, round, 1.5mm, 1.6mm, 3mm diameter")
      (libsource (lib "Electronic Devices_LIB") (part "TP_PAD_SMD_SMALL"))
    )
    (comp (ref "TP10")
      (value "NO COMPONENT")
      (footprint "TP_PAD_0.5MM_SMD_ROUND")
      (description "Test Point, SMD pad, round, 1.5mm, 1.6mm, 3mm diameter")
      (libsource (lib "Electronic Devices_LIB") (part "TP_PAD_SMD_SMALL"))
    )
    (comp (ref "TP11")
      (value "NO COMPONENT")
      (footprint "TP_PAD_0.5MM_SMD_ROUND")
      (description "Test Point, SMD pad, round, 1.5mm, 1.6mm, 3mm diameter")
      (libsource (lib "Electronic Devices_LIB") (part "TP_PAD_SMD_SMALL"))
    )
    (comp (ref "TP12")
      (value "NO COMPONENT")
      (footprint "TP_PAD_0.5MM_SMD_ROUND")
      (description "Test Point, SMD pad, round, 1.5mm, 1.6mm, 3mm diameter")
      (libsource (lib "Electronic Devices_LIB") (part "TP_PAD_SMD_SMALL"))
    )
    (comp (ref "TP13")
      (value "NO COMPONENT")
      (footprint "TP_PAD_0.5MM_SMD_ROUND")
      (description "Test Point, SMD pad, round, 1.5mm, 1.6mm, 3mm diameter")
      (libsource (lib "Electronic Devices_LIB") (part "TP_PAD_SMD_SMALL"))
    )
    (comp (ref "TP14")
      (value "NO COMPONENT")
      (footprint "TP_PAD_0.5MM_SMD_ROUND")
      (description "Test Point, SMD pad, round, 1.5mm, 1.6mm, 3mm diameter")
      (libsource (lib "Electronic Devices_LIB") (part "TP_PAD_SMD_SMALL"))
    )
    (comp (ref "TP15")
      (value "NO COMPONENT")
      (footprint "TP_PAD_0.5MM_SMD_ROUND")
      (description "Test Point, SMD pad, round, 1.5mm, 1.6mm, 3mm diameter")
      (libsource (lib "Electronic Devices_LIB") (part "TP_PAD_SMD_SMALL"))
    )
    (comp (ref "TP16")
      (value "NO COMPONENT")
      (footprint "TP_PAD_0.5MM_SMD_ROUND")
      (description "Test Point, SMD pad, round, 1.5mm, 1.6mm, 3mm diameter")
      (libsource (lib "Electronic Devices_LIB") (part "TP_PAD_SMD_SMALL"))
    )
    (comp (ref "TP17")
      (value "NO COMPONENT")
      (footprint "TP_PAD_0.5MM_SMD_ROUND")
      (description "Test Point, SMD pad, round, 1.5mm, 1.6mm, 3mm diameter")
      (libsource (lib "Electronic Devices_LIB") (part "TP_PAD_SMD_SMALL"))
    )
    (comp (ref "U2")
      (value "MPF7100BVMA1ES")
      (footprint "HVQFN48_SOT619-27D_NXP")
      (description "PMIC, i.MX8, 5 buck, 2 LDO RoHS Compliant: Yes")
      (fields (field (name "MANUFACTURER") "NXP Semiconductors"))
      (libsource (lib "Electronic Devices_LIB") (part "IC_PMIC_IMX8_MPF7100BVMA1ES"))
    )
  )
  (nets
    (net (code "3") (name "/PMIC_FSOB") (class "Default")
      (node (ref "R20") (pin "2") (pinfunction "2_2") (pintype "passive"))
      (node (ref "U2") (pin "36") (pinfunction "FSOB_36") (pintype "passive"))
    )
    (net (code "4") (name "/PMIC_I2C_SCL") (class "Default")
      (node (ref "U2") (pin "11") (pinfunction "SCL_11") (pintype "passive"))
    )
    (net (code "5") (name "/PMIC_I2C_SDA") (class "Default")
      (node (ref "U2") (pin "10") (pinfunction "SDA_10") (pintype "passive"))
    )
    (net (code "6") (name "/PMIC_INT_B") (class "Default")
      (node (ref "R18") (pin "1") (pinfunction "1_1") (pintype "passive"))
    )
    (net (code "7") (name "/PMIC_LDO2_EN") (class "Default")
      (node (ref "R10") (pin "1") (pinfunction "1_1") (pintype "passive"))
      (node (ref "R12") (pin "1") (pinfunction "1_1") (pintype "passive"))
      (node (ref "R14") (pin "2") (pinfunction "2_2") (pintype "passive"))
    )
    (net (code "8") (name "/PMIC_ON_REQ") (class "Default")
      (node (ref "R17") (pin "1") (pinfunction "1_1") (pintype "passive"))
    )
    (net (code "9") (name "/PMIC_PG") (class "Default")
      (node (ref "R23") (pin "1") (pinfunction "1_1") (pintype "passive"))
      (node (ref "TP13") (pin "1") (pinfunction "1_1") (pintype "passive"))
      (node (ref "U2") (pin "38") (pinfunction "PGOOD_38") (pintype "passive"))
    )
    (net (code "10") (name "/PMIC_RESETBMCU") (class "Default")
      (node (ref "R24") (pin "2") (pinfunction "2_2") (pintype "passive"))
      (node (ref "R26") (pin "2") (pinfunction "2_2") (pintype "passive"))
    )
    (net (code "11") (name "/PMIC_STBY") (class "Default")
      (node (ref "R15") (pin "1") (pinfunction "1_1") (pintype "passive"))
    )
    (net (code "12") (name "/PMIC_WDOG_IN") (class "Default")
      (node (ref "R19") (pin "1") (pinfunction "1_1") (pintype "passive"))
    )
    (net (code "13") (name "/SD1_VSELECT") (class "Default")
      (node (ref "R11") (pin "1") (pinfunction "1_1") (pintype "passive"))
      (node (ref "R13") (pin "2") (pinfunction "2_2") (pintype "passive"))
      (node (ref "R9") (pin "1") (pinfunction "1_1") (pintype "passive"))
    )
    (net (code "14") (name "/SW1FB") (class "Default")
      (node (ref "R4") (pin "1") (pinfunction "1_1") (pintype "passive"))
      (node (ref "U2") (pin "31") (pinfunction "SW1FB_31") (pintype "passive"))
    )
    (net (code "15") (name "/SW1LX") (class "Default")
      (node (ref "L1") (pin "1") (pinfunction "1_1") (pintype "passive"))
      (node (ref "U2") (pin "40") (pinfunction "SW1LX_40") (pintype "passive"))
    )
    (net (code "16") (name "/SW2FB") (class "Default")
      (node (ref "R5") (pin "1") (pinfunction "1_1") (pintype "passive"))
      (node (ref "U2") (pin "30") (pinfunction "SW2FB_30") (pintype "passive"))
    )
    (net (code "17") (name "/SW2LX") (class "Default")
      (node (ref "L2") (pin "1") (pinfunction "1_1") (pintype "passive"))
      (node (ref "U2") (pin "41") (pinfunction "SW2LX_41") (pintype "passive"))
    )
    (net (code "18") (name "/SW3FB") (class "Default")
      (node (ref "R6") (pin "1") (pinfunction "1_1") (pintype "passive"))
      (node (ref "U2") (pin "7") (pinfunction "SW3FB_7") (pintype "passive"))
    )
    (net (code "19") (name "/SW3LX") (class "Default")
      (node (ref "L3") (pin "1") (pinfunction "1_1") (pintype "passive"))
      (node (ref "U2") (pin "44") (pinfunction "SW3LX_44") (pintype "passive"))
    )
    (net (code "20") (name "/SW4FB") (class "Default")
      (node (ref "R7") (pin "1") (pinfunction "1_1") (pintype "passive"))
      (node (ref "U2") (pin "6") (pinfunction "SW4FB_6") (pintype "passive"))
    )
    (net (code "21") (name "/SW4LX") (class "Default")
      (node (ref "L4") (pin "1") (pinfunction "1_1") (pintype "passive"))
      (node (ref "U2") (pin "45") (pinfunction "SW4LX_45") (pintype "passive"))
    )
    (net (code "22") (name "/SW5FB") (class "Default")
      (node (ref "R8") (pin "1") (pinfunction "1_1") (pintype "passive"))
      (node (ref "U2") (pin "12") (pinfunction "SW5FB_12") (pintype "passive"))
    )
    (net (code "23") (name "/SW5LX") (class "Default")
      (node (ref "L5") (pin "1") (pinfunction "1_1") (pintype "passive"))
      (node (ref "U2") (pin "16") (pinfunction "SW5LX_16") (pintype "passive"))
    )
    (net (code "26") (name "1V8") (class "Default")
      (node (ref "R237") (pin "2") (pinfunction "2_2") (pintype "passive"))
    )
    (net (code "27") (name "3V3_PMIC") (class "Default")
      (node (ref "C39") (pin "2") (pinfunction "2_2") (pintype "passive"))
      (node (ref "C40") (pin "2") (pinfunction "2_2") (pintype "passive"))
      (node (ref "C41") (pin "2") (pinfunction "2_2") (pintype "passive"))
      (node (ref "C42") (pin "2") (pinfunction "2_2") (pintype "passive"))
      (node (ref "C43") (pin "2") (pinfunction "2_2") (pintype "passive"))
      (node (ref "C44") (pin "2") (pinfunction "2_2") (pintype "passive"))
      (node (ref "C46") (pin "2") (pinfunction "2_2") (pintype "passive"))
      (node (ref "R232") (pin "2") (pinfunction "2_2") (pintype "passive"))
      (node (ref "U2") (pin "15") (pinfunction "SW5IN_15") (pintype "passive"))
      (node (ref "U2") (pin "20") (pinfunction "LDO1IN_20") (pintype "passive"))
      (node (ref "U2") (pin "27") (pinfunction "VIN_27") (pintype "passive"))
      (node (ref "U2") (pin "39") (pinfunction "SW1IN_39") (pintype "passive"))
      (node (ref "U2") (pin "42") (pinfunction "SW2IN_42") (pintype "passive"))
      (node (ref "U2") (pin "43") (pinfunction "SW3IN_43") (pintype "passive"))
      (node (ref "U2") (pin "46") (pinfunction "SW4IN_46") (pintype "passive"))
    )
    (net (code "28") (name "3V3_PS") (class "Default")
      (node (ref "R232") (pin "1") (pinfunction "1_1") (pintype "passive"))
    )
    (net (code "29") (name "5V0_PS") (class "Default")
      (node (ref "C45") (pin "2") (pinfunction "2_2") (pintype "passive"))
      (node (ref "U2") (pin "19") (pinfunction "LDO2IN_19") (pintype "passive"))
    )
    (net (code "30") (name "GND") (class "Default")
      (node (ref "C39") (pin "1") (pinfunction "1_1") (pintype "passive"))
      (node (ref "C40") (pin "1") (pinfunction "1_1") (pintype "passive"))
      (node (ref "C41") (pin "1") (pinfunction "1_1") (pintype "passive"))
      (node (ref "C42") (pin "1") (pinfunction "1_1") (pintype "passive"))
      (node (ref "C43") (pin "1") (pinfunction "1_1") (pintype "passive"))
      (node (ref "C44") (pin "1") (pinfunction "1_1") (pintype "passive"))
      (node (ref "C45") (pin "1") (pinfunction "1_1") (pintype "passive"))
      (node (ref "C46") (pin "1") (pinfunction "1_1") (pintype "passive"))
      (node (ref "C47") (pin "1") (pinfunction "1_1") (pintype "passive"))
      (node (ref "C48") (pin "1") (pinfunction "1_1") (pintype "passive"))
      (node (ref "C49") (pin "1") (pinfunction "1_1") (pintype "passive"))
      (node (ref "C50") (pin "1") (pinfunction "1_1") (pintype "passive"))
      (node (ref "C51") (pin "1") (pinfunction "1_1") (pintype "passive"))
      (node (ref "C52") (pin "1") (pinfunction "1_1") (pintype "passive"))
      (node (ref "C53") (pin "1") (pinfunction "1_1") (pintype "passive"))
      (node (ref "C54") (pin "1") (pinfunction "1_1") (pintype "passive"))
      (node (ref "C55") (pin "1") (pinfunction "1_1") (pintype "passive"))
      (node (ref "C56") (pin "1") (pinfunction "1_1") (pintype "passive"))
      (node (ref "C57") (pin "1") (pinfunction "1_1") (pintype "passive"))
      (node (ref "C58") (pin "1") (pinfunction "1_1") (pintype "passive"))
      (node (ref "C59") (pin "1") (pinfunction "1_1") (pintype "passive"))
      (node (ref "C60") (pin "1") (pinfunction "1_1") (pintype "passive"))
      (node (ref "C61") (pin "1") (pinfunction "1_1") (pintype "passive"))
      (node (ref "C62") (pin "1") (pinfunction "1_1") (pintype "passive"))
      (node (ref "C63") (pin "1") (pinfunction "1_1") (pintype "passive"))
      (node (ref "C64") (pin "1") (pinfunction "1_1") (pintype "passive"))
      (node (ref "C65") (pin "1") (pinfunction "1_1") (pintype "passive"))
      (node (ref "C66") (pin "1") (pinfunction "1_1") (pintype "passive"))
      (node (ref "C67") (pin "1") (pinfunction "1_1") (pintype "passive"))
      (node (ref "C68") (pin "1") (pinfunction "1_1") (pintype "passive"))
      (node (ref "C69") (pin "1") (pinfunction "1_1") (pintype "passive"))
      (node (ref "C70") (pin "1") (pinfunction "1_1") (pintype "passive"))
      (node (ref "C71") (pin "1") (pinfunction "1_1") (pintype "passive"))
      (node (ref "C72") (pin "1") (pinfunction "1_1") (pintype "passive"))
      (node (ref "C73") (pin "1") (pinfunction "1_1") (pintype "passive"))
      (node (ref "R13") (pin "1") (pinfunction "1_1") (pintype "passive"))
      (node (ref "R14") (pin "1") (pinfunction "1_1") (pintype "passive"))
      (node (ref "R27") (pin "1") (pinfunction "1_1") (pintype "passive"))
      (node (ref "R28") (pin "1") (pinfunction "1_1") (pintype "passive"))
      (node (ref "R29") (pin "1") (pinfunction "1_1") (pintype "passive"))
      (node (ref "R30") (pin "1") (pinfunction "1_1") (pintype "passive"))
      (node (ref "U2") (pin "26") (pinfunction "AGND_26") (pintype "passive"))
      (node (ref "U2") (pin "29") (pinfunction "DGND_29") (pintype "passive"))
      (node (ref "U2") (pin "49") (pinfunction "EPAD_49") (pintype "passive"))
    )
    (net (code "31") (name "Net-(U2-AMUX)") (class "Default")
      (node (ref "TP15") (pin "1") (pinfunction "1_1") (pintype "passive"))
      (node (ref "U2") (pin "25") (pinfunction "AMUX_25") (pintype "passive"))
    )
    (net (code "32") (name "Net-(U2-EWARN)") (class "Default")
      (node (ref "R27") (pin "2") (pinfunction "2_2") (pintype "passive"))
      (node (ref "TP17") (pin "1") (pinfunction "1_1") (pintype "passive"))
      (node (ref "U2") (pin "3") (pinfunction "EWARN_3") (pintype "passive"))
    )
    (net (code "33") (name "Net-(U2-INTB)") (class "Default")
      (node (ref "R18") (pin "2") (pinfunction "2_2") (pintype "passive"))
      (node (ref "U2") (pin "37") (pinfunction "INTB_37") (pintype "passive"))
    )
    (net (code "34") (name "Net-(U2-LDO2EN)") (class "Default")
      (node (ref "R12") (pin "2") (pinfunction "2_2") (pintype "passive"))
      (node (ref "U2") (pin "4") (pinfunction "LDO2EN_4") (pintype "passive"))
    )
    (net (code "35") (name "Net-(U2-PWRON)") (class "Default")
      (node (ref "R17") (pin "2") (pinfunction "2_2") (pintype "passive"))
      (node (ref "U2") (pin "34") (pinfunction "PWRON_34") (pintype "passive"))
    )
    (net (code "36") (name "Net-(U2-RESETBMCU)") (class "Default")
      (node (ref "R26") (pin "1") (pinfunction "1_1") (pintype "passive"))
      (node (ref "U2") (pin "35") (pinfunction "RESETBMCU_35") (pintype "passive"))
    )
    (net (code "37") (name "Net-(U2-STANDBY)") (class "Default")
      (node (ref "R15") (pin "2") (pinfunction "2_2") (pintype "passive"))
      (node (ref "U2") (pin "33") (pinfunction "STANDBY_33") (pintype "passive"))
    )
    (net (code "38") (name "Net-(U2-SYNCIN)") (class "Default")
      (node (ref "R30") (pin "2") (pinfunction "2_2") (pintype "passive"))
      (node (ref "TP16") (pin "1") (pinfunction "1_1") (pintype "passive"))
      (node (ref "U2") (pin "5") (pinfunction "SYNCIN_5") (pintype "passive"))
    )
    (net (code "39") (name "Net-(U2-SYNCOUT)") (class "Default")
      (node (ref "TP14") (pin "1") (pinfunction "1_1") (pintype "passive"))
      (node (ref "U2") (pin "2") (pinfunction "SYNCOUT_2") (pintype "passive"))
    )
    (net (code "40") (name "Net-(U2-TBBEN)") (class "Default")
      (node (ref "R22") (pin "1") (pinfunction "1_1") (pintype "passive"))
      (node (ref "R29") (pin "2") (pinfunction "2_2") (pintype "passive"))
      (node (ref "U2") (pin "32") (pinfunction "TBBEN_32") (pintype "passive"))
    )
    (net (code "41") (name "Net-(U2-VDDOTP)") (class "Default")
      (node (ref "R21") (pin "1") (pinfunction "1_1") (pintype "passive"))
      (node (ref "R28") (pin "2") (pinfunction "2_2") (pintype "passive"))
      (node (ref "U2") (pin "8") (pinfunction "VDDOTP_8") (pintype "passive"))
    )
    (net (code "42") (name "Net-(U2-VSELECT)") (class "Default")
      (node (ref "R11") (pin "2") (pinfunction "2_2") (pintype "passive"))
      (node (ref "U2") (pin "48") (pinfunction "VSELECT_48") (pintype "passive"))
    )
    (net (code "43") (name "Net-(U2-VSNVS2)") (class "Default")
      (node (ref "R16") (pin "1") (pinfunction "1_1") (pintype "passive"))
      (node (ref "TP9") (pin "1") (pinfunction "1_1") (pintype "passive"))
      (node (ref "U2") (pin "22") (pinfunction "VSNVS2_22") (pintype "passive"))
    )
    (net (code "44") (name "Net-(U2-WDI)") (class "Default")
      (node (ref "R19") (pin "2") (pinfunction "2_2") (pintype "passive"))
      (node (ref "U2") (pin "1") (pinfunction "WDI_1") (pintype "passive"))
    )
    (net (code "45") (name "Net-(U2-XFAILB)") (class "Default")
      (node (ref "R25") (pin "1") (pinfunction "1_1") (pintype "passive"))
      (node (ref "U2") (pin "17") (pinfunction "XFAILB_17") (pintype "passive"))
    )
    (net (code "46") (name "PMIC_VDD_1V8") (class "Default")
      (node (ref "C47") (pin "2") (pinfunction "2_2") (pintype "passive"))
      (node (ref "C70") (pin "2") (pinfunction "2_2") (pintype "passive"))
      (node (ref "C71") (pin "2") (pinfunction "2_2") (pintype "passive"))
      (node (ref "C72") (pin "2") (pinfunction "2_2") (pintype "passive"))
      (node (ref "C73") (pin "2") (pinfunction "2_2") (pintype "passive"))
      (node (ref "L5") (pin "2") (pinfunction "2_2") (pintype "passive"))
      (node (ref "R10") (pin "2") (pinfunction "2_2") (pintype "passive"))
      (node (ref "R20") (pin "1") (pinfunction "1_1") (pintype "passive"))
      (node (ref "R23") (pin "2") (pinfunction "2_2") (pintype "passive"))
      (node (ref "R237") (pin "1") (pinfunction "1_1") (pintype "passive"))
      (node (ref "R24") (pin "1") (pinfunction "1_1") (pintype "passive"))
      (node (ref "R8") (pin "2") (pinfunction "2_2") (pintype "passive"))
      (node (ref "R9") (pin "2") (pinfunction "2_2") (pintype "passive"))
      (node (ref "TP5") (pin "1") (pinfunction "1_1") (pintype "passive"))
      (node (ref "U2") (pin "9") (pinfunction "VDDIO_9") (pintype "passive"))
    )
    (net (code "47") (name "PMIC_VDD_ANA") (class "Default")
      (node (ref "C48") (pin "2") (pinfunction "2_2") (pintype "passive"))
      (node (ref "TP6") (pin "1") (pinfunction "1_1") (pintype "passive"))
      (node (ref "U2") (pin "21") (pinfunction "LDO1OUT_21") (pintype "passive"))
    )
    (net (code "48") (name "PMIC_VDD_DDRIO") (class "Default")
      (node (ref "C66") (pin "2") (pinfunction "2_2") (pintype "passive"))
      (node (ref "C67") (pin "2") (pinfunction "2_2") (pintype "passive"))
      (node (ref "C68") (pin "2") (pinfunction "2_2") (pintype "passive"))
      (node (ref "C69") (pin "2") (pinfunction "2_2") (pintype "passive"))
      (node (ref "L4") (pin "2") (pinfunction "2_2") (pintype "passive"))
      (node (ref "R7") (pin "2") (pinfunction "2_2") (pintype "passive"))
      (node (ref "TP4") (pin "1") (pinfunction "1_1") (pintype "passive"))
    )
    (net (code "49") (name "PMIC_VDD_MAIN") (class "Default")
      (node (ref "C54") (pin "2") (pinfunction "2_2") (pintype "passive"))
      (node (ref "C55") (pin "2") (pinfunction "2_2") (pintype "passive"))
      (node (ref "C56") (pin "2") (pinfunction "2_2") (pintype "passive"))
      (node (ref "C57") (pin "2") (pinfunction "2_2") (pintype "passive"))
      (node (ref "L1") (pin "2") (pinfunction "2_2") (pintype "passive"))
      (node (ref "R4") (pin "2") (pinfunction "2_2") (pintype "passive"))
      (node (ref "TP1") (pin "1") (pinfunction "1_1") (pintype "passive"))
    )
    (net (code "50") (name "PMIC_VDD_MEMC") (class "Default")
      (node (ref "C58") (pin "2") (pinfunction "2_2") (pintype "passive"))
      (node (ref "C59") (pin "2") (pinfunction "2_2") (pintype "passive"))
      (node (ref "C60") (pin "2") (pinfunction "2_2") (pintype "passive"))
      (node (ref "C61") (pin "2") (pinfunction "2_2") (pintype "passive"))
      (node (ref "L2") (pin "2") (pinfunction "2_2") (pintype "passive"))
      (node (ref "R5") (pin "2") (pinfunction "2_2") (pintype "passive"))
      (node (ref "TP2") (pin "1") (pinfunction "1_1") (pintype "passive"))
    )
    (net (code "51") (name "PMIC_VDD_SD") (class "Default")
      (node (ref "C49") (pin "2") (pinfunction "2_2") (pintype "passive"))
      (node (ref "TP7") (pin "1") (pinfunction "1_1") (pintype "passive"))
      (node (ref "U2") (pin "18") (pinfunction "LDO2OUT_18") (pintype "passive"))
    )
    (net (code "52") (name "PMIC_VDD_SNVS1") (class "Default")
      (node (ref "C51") (pin "2") (pinfunction "2_2") (pintype "passive"))
      (node (ref "TP8") (pin "1") (pinfunction "1_1") (pintype "passive"))
      (node (ref "U2") (pin "23") (pinfunction "VSNVS1_23") (pintype "passive"))
    )
    (net (code "53") (name "PMIC_VDD_SNVS2") (class "Default")
      (node (ref "C50") (pin "2") (pinfunction "2_2") (pintype "passive"))
      (node (ref "R16") (pin "2") (pinfunction "2_2") (pintype "passive"))
      (node (ref "TP10") (pin "1") (pinfunction "1_1") (pintype "passive"))
    )
    (net (code "54") (name "PMIC_VDD_V2X_VTT") (class "Default")
      (node (ref "C62") (pin "2") (pinfunction "2_2") (pintype "passive"))
      (node (ref "C63") (pin "2") (pinfunction "2_2") (pintype "passive"))
      (node (ref "C64") (pin "2") (pinfunction "2_2") (pintype "passive"))
      (node (ref "C65") (pin "2") (pinfunction "2_2") (pintype "passive"))
      (node (ref "L3") (pin "2") (pinfunction "2_2") (pintype "passive"))
      (node (ref "R6") (pin "2") (pinfunction "2_2") (pintype "passive"))
      (node (ref "TP3") (pin "1") (pinfunction "1_1") (pintype "passive"))
    )
    (net (code "55") (name "V1P5A_1V5") (class "Default")
      (node (ref "C52") (pin "2") (pinfunction "2_2") (pintype "passive"))
      (node (ref "R25") (pin "2") (pinfunction "2_2") (pintype "passive"))
      (node (ref "TP11") (pin "1") (pinfunction "1_1") (pintype "passive"))
      (node (ref "U2") (pin "24") (pinfunction "V1P5A_24") (pintype "passive"))
    )
    (net (code "56") (name "V1P5D_1V5") (class "Default")
      (node (ref "C53") (pin "2") (pinfunction "2_2") (pintype "passive"))
      (node (ref "R21") (pin "2") (pinfunction "2_2") (pintype "passive"))
      (node (ref "R22") (pin "2") (pinfunction "2_2") (pintype "passive"))
      (node (ref "TP12") (pin "1") (pinfunction "1_1") (pintype "passive"))
      (node (ref "U2") (pin "28") (pinfunction "V1P5D_28") (pintype "passive"))
    )
    (net (code "57") (name "unconnected-(U2-NC-Pad47)") (class "Default")
      (node (ref "U2") (pin "47") (pinfunction "NC_47") (pintype "passive+no_connect"))
    )
    (net (code "58") (name "unconnected-(U2-NC1-Pad14)") (class "Default")
      (node (ref "U2") (pin "14") (pinfunction "NC1_14") (pintype "passive+no_connect"))
    )
    (net (code "59") (name "unconnected-(U2-XINTB-Pad13)") (class "Default")
      (node (ref "U2") (pin "13") (pinfunction "XINTB_13") (pintype "passive+no_connect"))
    )
  )
)
